# Connectors1.net
KiCad netlist of a schematic drawn in Altium Designer
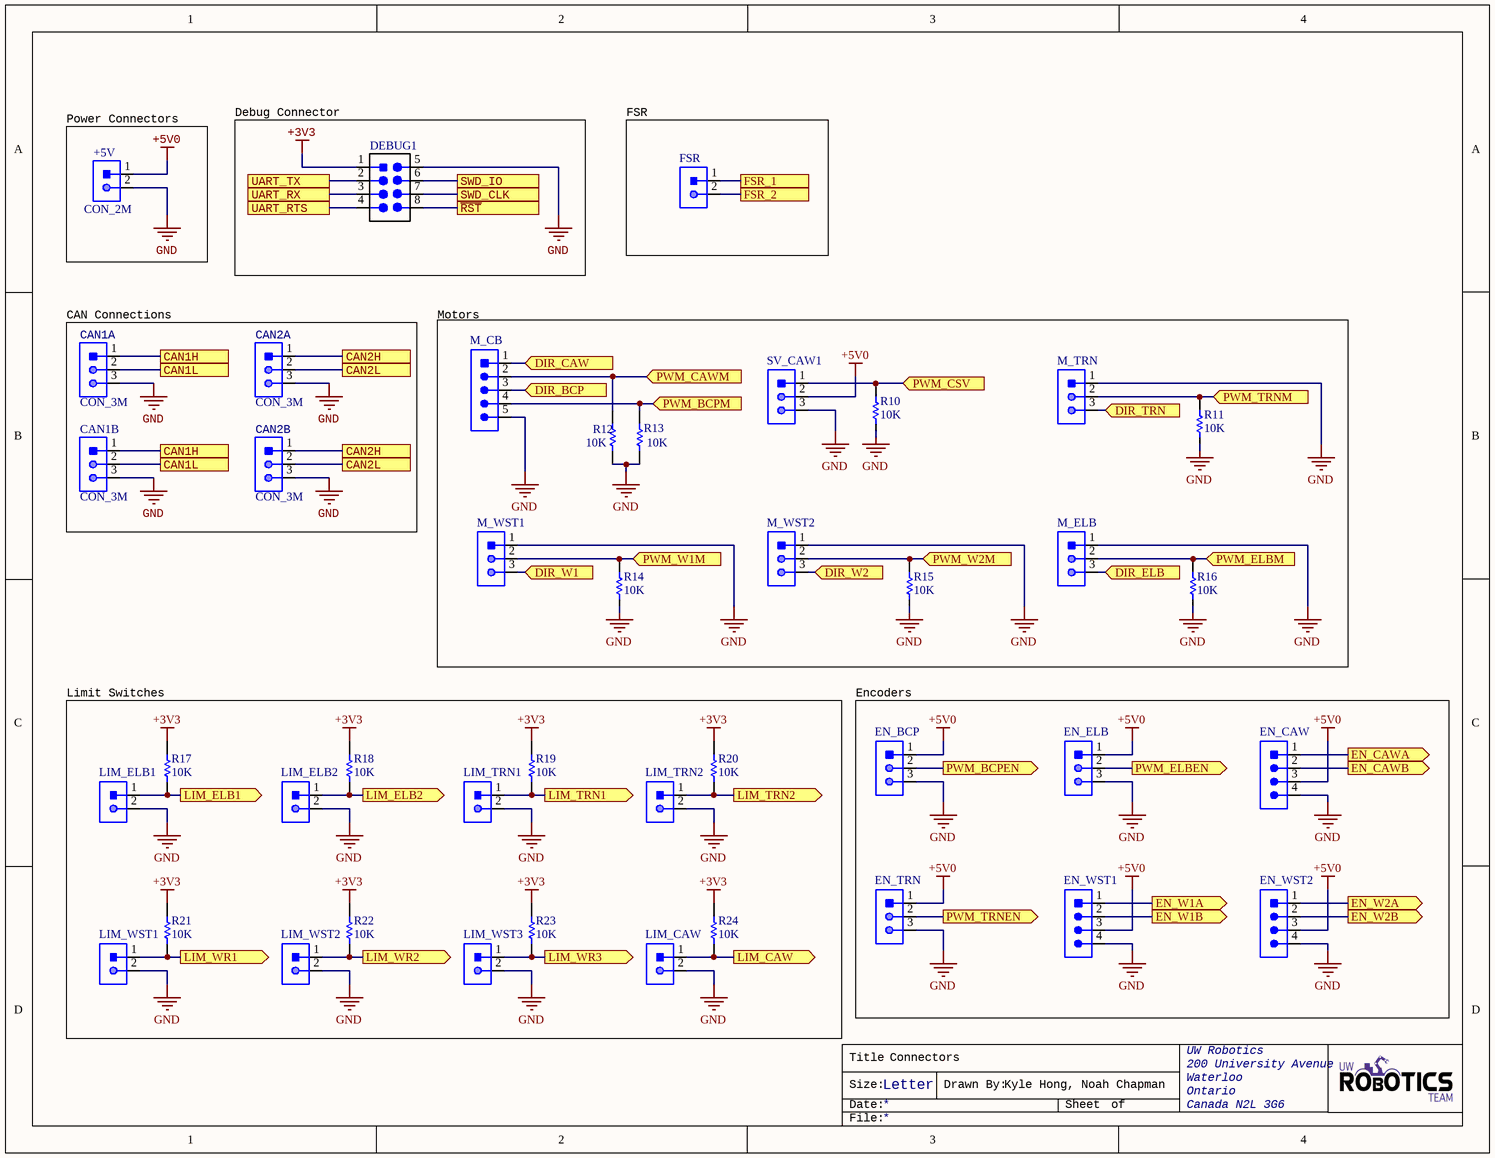
[diagram p0: Connectors1.SchDoc]

(export (version "E")
  (design (tool "Eeschema 10.0.6"))
  (components
    (comp (ref "+5V")
      (value "CON_2M")
      (footprint "JST-B2B-PHSK")
      (libsource (lib "UWRT_Schematic_Library_2020") (part "CON_2M"))
    )
    (comp (ref "CAN1A")
      (value "CON_3M")
      (footprint "JST-B3B-SM4-TB")
      (libsource (lib "UWRT_Schematic_Library_2020") (part "CON_3M"))
    )
    (comp (ref "CAN1B")
      (value "CON_3M")
      (footprint "JST-B3B-SM4-TB")
      (libsource (lib "UWRT_Schematic_Library_2020") (part "CON_3M"))
    )
    (comp (ref "CAN2A")
      (value "CON_3M")
      (footprint "JST-B3B-SM4-TB")
      (libsource (lib "UWRT_Schematic_Library_2020") (part "CON_3M"))
    )
    (comp (ref "CAN2B")
      (value "CON_3M")
      (footprint "JST-B3B-SM4-TB")
      (libsource (lib "UWRT_Schematic_Library_2020") (part "CON_3M"))
    )
    (comp (ref "DEBUG1")
      (value "HEADER 4X2")
      (footprint "HEADER_2X4")
      (description "Header, 4-Pin Dual row")
      (fields (field (name "MPN") "GRPB042VWVN-RC") (field (name "DIGIKEY PART NUMBER") "S9015E-04-ND"))
      (libsource (lib "UWRT_Schematic_Library_2020") (part "HEADER 4X2"))
    )
    (comp (ref "EN_BCP")
      (value "CON_3M")
      (footprint "JST-B3B-SM4-TB")
      (libsource (lib "UWRT_Schematic_Library_2020") (part "CON_3M"))
    )
    (comp (ref "EN_CAW")
      (value "CON_4M")
      (footprint "JST-B4B-PHSK")
      (libsource (lib "UWRT_Schematic_Library_2020") (part "CON_4M"))
    )
    (comp (ref "EN_ELB")
      (value "CON_3M")
      (footprint "JST-B3B-SM4-TB")
      (libsource (lib "UWRT_Schematic_Library_2020") (part "CON_3M"))
    )
    (comp (ref "EN_TRN")
      (value "CON_3M")
      (footprint "JST-B3B-SM4-TB")
      (libsource (lib "UWRT_Schematic_Library_2020") (part "CON_3M"))
    )
    (comp (ref "EN_WST1")
      (value "CON_4M")
      (footprint "JST-B4B-PHSK")
      (libsource (lib "UWRT_Schematic_Library_2020") (part "CON_4M"))
    )
    (comp (ref "EN_WST2")
      (value "CON_4M")
      (footprint "JST-B4B-PHSK")
      (libsource (lib "UWRT_Schematic_Library_2020") (part "CON_4M"))
    )
    (comp (ref "FSR")
      (value "CON_2M")
      (footprint "JST-B2B-PHSK")
      (libsource (lib "UWRT_Schematic_Library_2020") (part "CON_2M"))
    )
    (comp (ref "LIM_CAW")
      (value "CON_2M")
      (footprint "JST-B2B-PHSK")
      (libsource (lib "UWRT_Schematic_Library_2020") (part "CON_2M"))
    )
    (comp (ref "LIM_ELB1")
      (value "CON_2M")
      (footprint "JST-B2B-PHSK")
      (libsource (lib "UWRT_Schematic_Library_2020") (part "CON_2M"))
    )
    (comp (ref "LIM_ELB2")
      (value "CON_2M")
      (footprint "JST-B2B-PHSK")
      (libsource (lib "UWRT_Schematic_Library_2020") (part "CON_2M"))
    )
    (comp (ref "LIM_TRN1")
      (value "CON_2M")
      (footprint "JST-B2B-PHSK")
      (libsource (lib "UWRT_Schematic_Library_2020") (part "CON_2M"))
    )
    (comp (ref "LIM_TRN2")
      (value "CON_2M")
      (footprint "JST-B2B-PHSK")
      (libsource (lib "UWRT_Schematic_Library_2020") (part "CON_2M"))
    )
    (comp (ref "LIM_WST1")
      (value "CON_2M")
      (footprint "JST-B2B-PHSK")
      (libsource (lib "UWRT_Schematic_Library_2020") (part "CON_2M"))
    )
    (comp (ref "LIM_WST2")
      (value "CON_2M")
      (footprint "JST-B2B-PHSK")
      (libsource (lib "UWRT_Schematic_Library_2020") (part "CON_2M"))
    )
    (comp (ref "LIM_WST3")
      (value "CON_2M")
      (footprint "JST-B2B-PHSK")
      (libsource (lib "UWRT_Schematic_Library_2020") (part "CON_2M"))
    )
    (comp (ref "M_CB")
      (value "CON_5M")
      (footprint "JST-B5B-PHSK")
      (libsource (lib "UWRT_Schematic_Library_2020") (part "CON_5M"))
    )
    (comp (ref "M_ELB")
      (value "CON_3M")
      (footprint "JST-B3B-SM4-TB")
      (libsource (lib "UWRT_Schematic_Library_2020") (part "CON_3M"))
    )
    (comp (ref "M_TRN")
      (value "CON_3M")
      (footprint "JST-B3B-SM4-TB")
      (libsource (lib "UWRT_Schematic_Library_2020") (part "CON_3M"))
    )
    (comp (ref "M_WST1")
      (value "CON_3M")
      (footprint "JST-B3B-SM4-TB")
      (libsource (lib "UWRT_Schematic_Library_2020") (part "CON_3M"))
    )
    (comp (ref "M_WST2")
      (value "CON_3M")
      (footprint "JST-B3B-SM4-TB")
      (libsource (lib "UWRT_Schematic_Library_2020") (part "CON_3M"))
    )
    (comp (ref "R10")
      (value "10K")
      (footprint "RESC0603(1608)_N")
      (description "RES SMD 10K OHM 5% 1/10W 0603")
      (fields (field (name "MANUFACTURER") "Yageo") (field (name "MPN") "RC0603JR-0710KL"))
      (libsource (lib "UWRT_Schematic_Library_2020") (part "RES_10K_0603"))
    )
    (comp (ref "R11")
      (value "10K")
      (footprint "RESC0603(1608)_N")
      (description "RES SMD 10K OHM 5% 1/10W 0603")
      (fields (field (name "MANUFACTURER") "Yageo") (field (name "MPN") "RC0603JR-0710KL"))
      (libsource (lib "UWRT_Schematic_Library_2020") (part "RES_10K_0603"))
    )
    (comp (ref "R12")
      (value "10K")
      (footprint "RESC0603(1608)_N")
      (description "RES SMD 10K OHM 5% 1/10W 0603")
      (fields (field (name "MANUFACTURER") "Yageo") (field (name "MPN") "RC0603JR-0710KL"))
      (libsource (lib "UWRT_Schematic_Library_2020") (part "RES_10K_0603"))
    )
    (comp (ref "R13")
      (value "10K")
      (footprint "RESC0603(1608)_N")
      (description "RES SMD 10K OHM 5% 1/10W 0603")
      (fields (field (name "MANUFACTURER") "Yageo") (field (name "MPN") "RC0603JR-0710KL"))
      (libsource (lib "UWRT_Schematic_Library_2020") (part "RES_10K_0603"))
    )
    (comp (ref "R14")
      (value "10K")
      (footprint "RESC0603(1608)_N")
      (description "RES SMD 10K OHM 5% 1/10W 0603")
      (fields (field (name "MANUFACTURER") "Yageo") (field (name "MPN") "RC0603JR-0710KL"))
      (libsource (lib "UWRT_Schematic_Library_2020") (part "RES_10K_0603"))
    )
    (comp (ref "R15")
      (value "10K")
      (footprint "RESC0603(1608)_N")
      (description "RES SMD 10K OHM 5% 1/10W 0603")
      (fields (field (name "MANUFACTURER") "Yageo") (field (name "MPN") "RC0603JR-0710KL"))
      (libsource (lib "UWRT_Schematic_Library_2020") (part "RES_10K_0603"))
    )
    (comp (ref "R16")
      (value "10K")
      (footprint "RESC0603(1608)_N")
      (description "RES SMD 10K OHM 5% 1/10W 0603")
      (fields (field (name "MANUFACTURER") "Yageo") (field (name "MPN") "RC0603JR-0710KL"))
      (libsource (lib "UWRT_Schematic_Library_2020") (part "RES_10K_0603"))
    )
    (comp (ref "R17")
      (value "10K")
      (footprint "RESC0603(1608)_N")
      (description "RES SMD 10K OHM 5% 1/10W 0603")
      (fields (field (name "MANUFACTURER") "Yageo") (field (name "MPN") "RC0603JR-0710KL"))
      (libsource (lib "UWRT_Schematic_Library_2020") (part "RES_10K_0603"))
    )
    (comp (ref "R18")
      (value "10K")
      (footprint "RESC0603(1608)_N")
      (description "RES SMD 10K OHM 5% 1/10W 0603")
      (fields (field (name "MANUFACTURER") "Yageo") (field (name "MPN") "RC0603JR-0710KL"))
      (libsource (lib "UWRT_Schematic_Library_2020") (part "RES_10K_0603"))
    )
    (comp (ref "R19")
      (value "10K")
      (footprint "RESC0603(1608)_N")
      (description "RES SMD 10K OHM 5% 1/10W 0603")
      (fields (field (name "MANUFACTURER") "Yageo") (field (name "MPN") "RC0603JR-0710KL"))
      (libsource (lib "UWRT_Schematic_Library_2020") (part "RES_10K_0603"))
    )
    (comp (ref "R20")
      (value "10K")
      (footprint "RESC0603(1608)_N")
      (description "RES SMD 10K OHM 5% 1/10W 0603")
      (fields (field (name "MANUFACTURER") "Yageo") (field (name "MPN") "RC0603JR-0710KL"))
      (libsource (lib "UWRT_Schematic_Library_2020") (part "RES_10K_0603"))
    )
    (comp (ref "R21")
      (value "10K")
      (footprint "RESC0603(1608)_N")
      (description "RES SMD 10K OHM 5% 1/10W 0603")
      (fields (field (name "MANUFACTURER") "Yageo") (field (name "MPN") "RC0603JR-0710KL"))
      (libsource (lib "UWRT_Schematic_Library_2020") (part "RES_10K_0603"))
    )
    (comp (ref "R22")
      (value "10K")
      (footprint "RESC0603(1608)_N")
      (description "RES SMD 10K OHM 5% 1/10W 0603")
      (fields (field (name "MANUFACTURER") "Yageo") (field (name "MPN") "RC0603JR-0710KL"))
      (libsource (lib "UWRT_Schematic_Library_2020") (part "RES_10K_0603"))
    )
    (comp (ref "R23")
      (value "10K")
      (footprint "RESC0603(1608)_N")
      (description "RES SMD 10K OHM 5% 1/10W 0603")
      (fields (field (name "MANUFACTURER") "Yageo") (field (name "MPN") "RC0603JR-0710KL"))
      (libsource (lib "UWRT_Schematic_Library_2020") (part "RES_10K_0603"))
    )
    (comp (ref "R24")
      (value "10K")
      (footprint "RESC0603(1608)_N")
      (description "RES SMD 10K OHM 5% 1/10W 0603")
      (fields (field (name "MANUFACTURER") "Yageo") (field (name "MPN") "RC0603JR-0710KL"))
      (libsource (lib "UWRT_Schematic_Library_2020") (part "RES_10K_0603"))
    )
    (comp (ref "SV_CAW1")
      (value "CON_3M")
      (footprint "JST-B3B-SM4-TB")
      (libsource (lib "UWRT_Schematic_Library_2020") (part "CON_3M"))
    )
  )
  (nets
    (net (code "1") (name "+3V3") (class "Default")
      (node (ref "DEBUG1") (pin "1") (pinfunction "VCC_1") (pintype "passive"))
      (node (ref "R17") (pin "2") (pinfunction "2_2") (pintype "passive"))
      (node (ref "R18") (pin "2") (pinfunction "2_2") (pintype "passive"))
      (node (ref "R19") (pin "2") (pinfunction "2_2") (pintype "passive"))
      (node (ref "R20") (pin "2") (pinfunction "2_2") (pintype "passive"))
      (node (ref "R21") (pin "2") (pinfunction "2_2") (pintype "passive"))
      (node (ref "R22") (pin "2") (pinfunction "2_2") (pintype "passive"))
      (node (ref "R23") (pin "2") (pinfunction "2_2") (pintype "passive"))
      (node (ref "R24") (pin "2") (pinfunction "2_2") (pintype "passive"))
    )
    (net (code "2") (name "+5V0") (class "Default")
      (node (ref "+5V") (pin "1") (pinfunction "1_1") (pintype "passive"))
      (node (ref "EN_BCP") (pin "1") (pinfunction "1_1") (pintype "passive"))
      (node (ref "EN_CAW") (pin "3") (pinfunction "3_3") (pintype "passive"))
      (node (ref "EN_ELB") (pin "1") (pinfunction "1_1") (pintype "passive"))
      (node (ref "EN_TRN") (pin "1") (pinfunction "1_1") (pintype "passive"))
      (node (ref "EN_WST1") (pin "3") (pinfunction "3_3") (pintype "passive"))
      (node (ref "EN_WST2") (pin "3") (pinfunction "3_3") (pintype "passive"))
      (node (ref "SV_CAW1") (pin "2") (pinfunction "2_2") (pintype "passive"))
    )
    (net (code "3") (name "/CAN1H") (class "Default")
      (node (ref "CAN1A") (pin "1") (pinfunction "1_1") (pintype "passive"))
      (node (ref "CAN1B") (pin "1") (pinfunction "1_1") (pintype "passive"))
    )
    (net (code "4") (name "/CAN1L") (class "Default")
      (node (ref "CAN1A") (pin "2") (pinfunction "2_2") (pintype "passive"))
      (node (ref "CAN1B") (pin "2") (pinfunction "2_2") (pintype "passive"))
    )
    (net (code "5") (name "/CAN2H") (class "Default")
      (node (ref "CAN2A") (pin "1") (pinfunction "1_1") (pintype "passive"))
      (node (ref "CAN2B") (pin "1") (pinfunction "1_1") (pintype "passive"))
    )
    (net (code "6") (name "/CAN2L") (class "Default")
      (node (ref "CAN2A") (pin "2") (pinfunction "2_2") (pintype "passive"))
      (node (ref "CAN2B") (pin "2") (pinfunction "2_2") (pintype "passive"))
    )
    (net (code "7") (name "/DIR_BCP") (class "Default")
      (node (ref "M_CB") (pin "3") (pinfunction "3_3") (pintype "passive"))
    )
    (net (code "8") (name "/DIR_CAW") (class "Default")
      (node (ref "M_CB") (pin "1") (pinfunction "1_1") (pintype "passive"))
    )
    (net (code "9") (name "/DIR_ELB") (class "Default")
      (node (ref "M_ELB") (pin "3") (pinfunction "3_3") (pintype "passive"))
    )
    (net (code "10") (name "/DIR_TRN") (class "Default")
      (node (ref "M_TRN") (pin "3") (pinfunction "3_3") (pintype "passive"))
    )
    (net (code "11") (name "/DIR_W1") (class "Default")
      (node (ref "M_WST1") (pin "3") (pinfunction "3_3") (pintype "passive"))
    )
    (net (code "12") (name "/DIR_W2") (class "Default")
      (node (ref "M_WST2") (pin "3") (pinfunction "3_3") (pintype "passive"))
    )
    (net (code "13") (name "/EN_CAWA") (class "Default")
      (node (ref "EN_CAW") (pin "1") (pinfunction "1_1") (pintype "passive"))
    )
    (net (code "14") (name "/EN_CAWB") (class "Default")
      (node (ref "EN_CAW") (pin "2") (pinfunction "2_2") (pintype "passive"))
    )
    (net (code "15") (name "/EN_W1A") (class "Default")
      (node (ref "EN_WST1") (pin "1") (pinfunction "1_1") (pintype "passive"))
    )
    (net (code "16") (name "/EN_W1B") (class "Default")
      (node (ref "EN_WST1") (pin "2") (pinfunction "2_2") (pintype "passive"))
    )
    (net (code "17") (name "/EN_W2A") (class "Default")
      (node (ref "EN_WST2") (pin "1") (pinfunction "1_1") (pintype "passive"))
    )
    (net (code "18") (name "/EN_W2B") (class "Default")
      (node (ref "EN_WST2") (pin "2") (pinfunction "2_2") (pintype "passive"))
    )
    (net (code "19") (name "/FSR_1") (class "Default")
      (node (ref "FSR") (pin "1") (pinfunction "1_1") (pintype "passive"))
    )
    (net (code "20") (name "/FSR_2") (class "Default")
      (node (ref "FSR") (pin "2") (pinfunction "2_2") (pintype "passive"))
    )
    (net (code "21") (name "/LIM_CAW") (class "Default")
      (node (ref "LIM_CAW") (pin "1") (pinfunction "1_1") (pintype "passive"))
      (node (ref "R24") (pin "1") (pinfunction "1_1") (pintype "passive"))
    )
    (net (code "22") (name "/LIM_ELB1") (class "Default")
      (node (ref "LIM_ELB1") (pin "1") (pinfunction "1_1") (pintype "passive"))
      (node (ref "R17") (pin "1") (pinfunction "1_1") (pintype "passive"))
    )
    (net (code "23") (name "/LIM_ELB2") (class "Default")
      (node (ref "LIM_ELB2") (pin "1") (pinfunction "1_1") (pintype "passive"))
      (node (ref "R18") (pin "1") (pinfunction "1_1") (pintype "passive"))
    )
    (net (code "24") (name "/LIM_TRN1") (class "Default")
      (node (ref "LIM_TRN1") (pin "1") (pinfunction "1_1") (pintype "passive"))
      (node (ref "R19") (pin "1") (pinfunction "1_1") (pintype "passive"))
    )
    (net (code "25") (name "/LIM_TRN2") (class "Default")
      (node (ref "LIM_TRN2") (pin "1") (pinfunction "1_1") (pintype "passive"))
      (node (ref "R20") (pin "1") (pinfunction "1_1") (pintype "passive"))
    )
    (net (code "26") (name "/LIM_WR1") (class "Default")
      (node (ref "LIM_WST1") (pin "1") (pinfunction "1_1") (pintype "passive"))
      (node (ref "R21") (pin "1") (pinfunction "1_1") (pintype "passive"))
    )
    (net (code "27") (name "/LIM_WR2") (class "Default")
      (node (ref "LIM_WST2") (pin "1") (pinfunction "1_1") (pintype "passive"))
      (node (ref "R22") (pin "1") (pinfunction "1_1") (pintype "passive"))
    )
    (net (code "28") (name "/LIM_WR3") (class "Default")
      (node (ref "LIM_WST3") (pin "1") (pinfunction "1_1") (pintype "passive"))
      (node (ref "R23") (pin "1") (pinfunction "1_1") (pintype "passive"))
    )
    (net (code "29") (name "/PWM_BCPEN") (class "Default")
      (node (ref "EN_BCP") (pin "2") (pinfunction "2_2") (pintype "passive"))
    )
    (net (code "30") (name "/PWM_BCPM") (class "Default")
      (node (ref "M_CB") (pin "4") (pinfunction "4_4") (pintype "passive"))
      (node (ref "R13") (pin "2") (pinfunction "2_2") (pintype "passive"))
    )
    (net (code "31") (name "/PWM_CAWM") (class "Default")
      (node (ref "M_CB") (pin "2") (pinfunction "2_2") (pintype "passive"))
      (node (ref "R12") (pin "2") (pinfunction "2_2") (pintype "passive"))
    )
    (net (code "32") (name "/PWM_CSV") (class "Default")
      (node (ref "R10") (pin "2") (pinfunction "2_2") (pintype "passive"))
      (node (ref "SV_CAW1") (pin "1") (pinfunction "1_1") (pintype "passive"))
    )
    (net (code "33") (name "/PWM_ELBEN") (class "Default")
      (node (ref "EN_ELB") (pin "2") (pinfunction "2_2") (pintype "passive"))
    )
    (net (code "34") (name "/PWM_ELBM") (class "Default")
      (node (ref "M_ELB") (pin "2") (pinfunction "2_2") (pintype "passive"))
      (node (ref "R16") (pin "2") (pinfunction "2_2") (pintype "passive"))
    )
    (net (code "35") (name "/PWM_TRNEN") (class "Default")
      (node (ref "EN_TRN") (pin "2") (pinfunction "2_2") (pintype "passive"))
    )
    (net (code "36") (name "/PWM_TRNM") (class "Default")
      (node (ref "M_TRN") (pin "2") (pinfunction "2_2") (pintype "passive"))
      (node (ref "R11") (pin "2") (pinfunction "2_2") (pintype "passive"))
    )
    (net (code "37") (name "/PWM_W1M") (class "Default")
      (node (ref "M_WST1") (pin "2") (pinfunction "2_2") (pintype "passive"))
      (node (ref "R14") (pin "2") (pinfunction "2_2") (pintype "passive"))
    )
    (net (code "38") (name "/PWM_W2M") (class "Default")
      (node (ref "M_WST2") (pin "2") (pinfunction "2_2") (pintype "passive"))
      (node (ref "R15") (pin "2") (pinfunction "2_2") (pintype "passive"))
    )
    (net (code "39") (name "/SWD_CLK") (class "Default")
      (node (ref "DEBUG1") (pin "7") (pinfunction "3_7") (pintype "passive"))
    )
    (net (code "40") (name "/SWD_IO") (class "Default")
      (node (ref "DEBUG1") (pin "6") (pinfunction "2_6") (pintype "passive"))
    )
    (net (code "41") (name "/UART_RTS") (class "Default")
      (node (ref "DEBUG1") (pin "4") (pinfunction "4_4") (pintype "passive"))
    )
    (net (code "42") (name "/UART_RX") (class "Default")
      (node (ref "DEBUG1") (pin "3") (pinfunction "3_3") (pintype "passive"))
    )
    (net (code "43") (name "/UART_TX") (class "Default")
      (node (ref "DEBUG1") (pin "2") (pinfunction "2_2") (pintype "passive"))
    )
    (net (code "44") (name "/~{RST}") (class "Default")
      (node (ref "DEBUG1") (pin "8") (pinfunction "4_8") (pintype "passive"))
    )
    (net (code "45") (name "GND") (class "Default")
      (node (ref "+5V") (pin "2") (pinfunction "2_2") (pintype "passive"))
      (node (ref "CAN1A") (pin "3") (pinfunction "3_3") (pintype "passive"))
      (node (ref "CAN1B") (pin "3") (pinfunction "3_3") (pintype "passive"))
      (node (ref "CAN2A") (pin "3") (pinfunction "3_3") (pintype "passive"))
      (node (ref "CAN2B") (pin "3") (pinfunction "3_3") (pintype "passive"))
      (node (ref "DEBUG1") (pin "5") (pinfunction "GND_5") (pintype "passive"))
      (node (ref "EN_BCP") (pin "3") (pinfunction "3_3") (pintype "passive"))
      (node (ref "EN_CAW") (pin "4") (pinfunction "4_4") (pintype "passive"))
      (node (ref "EN_ELB") (pin "3") (pinfunction "3_3") (pintype "passive"))
      (node (ref "EN_TRN") (pin "3") (pinfunction "3_3") (pintype "passive"))
      (node (ref "EN_WST1") (pin "4") (pinfunction "4_4") (pintype "passive"))
      (node (ref "EN_WST2") (pin "4") (pinfunction "4_4") (pintype "passive"))
      (node (ref "LIM_CAW") (pin "2") (pinfunction "2_2") (pintype "passive"))
      (node (ref "LIM_ELB1") (pin "2") (pinfunction "2_2") (pintype "passive"))
      (node (ref "LIM_ELB2") (pin "2") (pinfunction "2_2") (pintype "passive"))
      (node (ref "LIM_TRN1") (pin "2") (pinfunction "2_2") (pintype "passive"))
      (node (ref "LIM_TRN2") (pin "2") (pinfunction "2_2") (pintype "passive"))
      (node (ref "LIM_WST1") (pin "2") (pinfunction "2_2") (pintype "passive"))
      (node (ref "LIM_WST2") (pin "2") (pinfunction "2_2") (pintype "passive"))
      (node (ref "LIM_WST3") (pin "2") (pinfunction "2_2") (pintype "passive"))
      (node (ref "M_CB") (pin "5") (pinfunction "5_5") (pintype "passive"))
      (node (ref "M_ELB") (pin "1") (pinfunction "1_1") (pintype "passive"))
      (node (ref "M_TRN") (pin "1") (pinfunction "1_1") (pintype "passive"))
      (node (ref "M_WST1") (pin "1") (pinfunction "1_1") (pintype "passive"))
      (node (ref "M_WST2") (pin "1") (pinfunction "1_1") (pintype "passive"))
      (node (ref "R10") (pin "1") (pinfunction "1_1") (pintype "passive"))
      (node (ref "R11") (pin "1") (pinfunction "1_1") (pintype "passive"))
      (node (ref "R12") (pin "1") (pinfunction "1_1") (pintype "passive"))
      (node (ref "R13") (pin "1") (pinfunction "1_1") (pintype "passive"))
      (node (ref "R14") (pin "1") (pinfunction "1_1") (pintype "passive"))
      (node (ref "R15") (pin "1") (pinfunction "1_1") (pintype "passive"))
      (node (ref "R16") (pin "1") (pinfunction "1_1") (pintype "passive"))
      (node (ref "SV_CAW1") (pin "3") (pinfunction "3_3") (pintype "passive"))
    )
  )
)
